# Eagle_4-Channel_Relay_Driver_Circuit.net
KiCad netlist of a schematic drawn in EAGLE
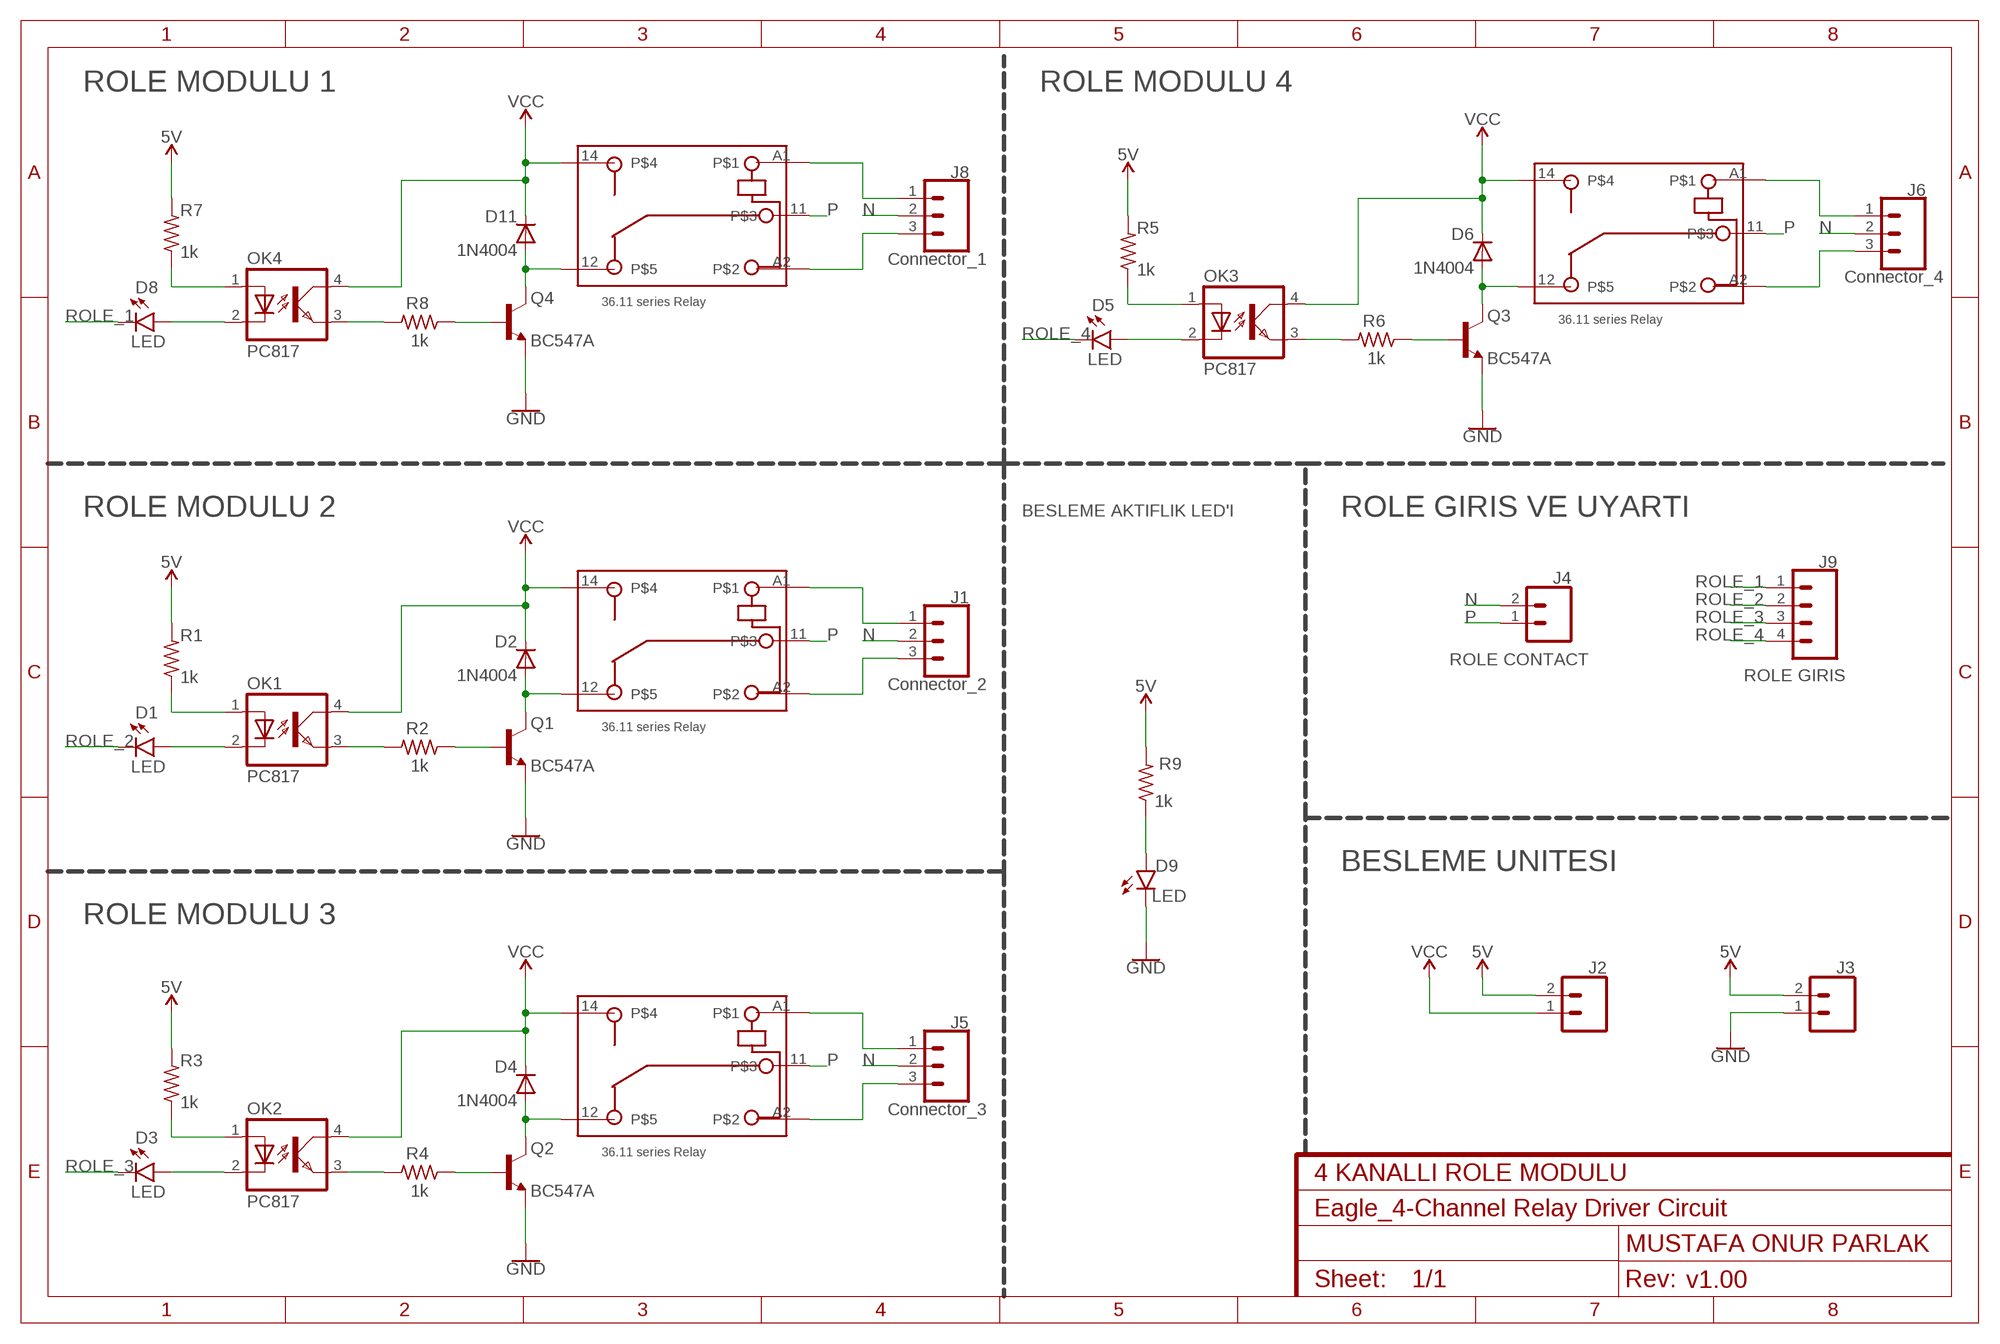
[diagram p0: schematic, sheet 1]

(export (version "E")
  (design (tool "Eeschema 10.0.6"))
  (components
    (comp (ref "D1")
      (value "LED")
      (footprint "eagle-import:LED_3MM")
      (libsource (lib "eagle-import") (part "LED3MM"))
    )
    (comp (ref "D2")
      (value "1N4004")
      (footprint "eagle-import:DO41-10")
      (libsource (lib "eagle-import") (part "1N4004"))
    )
    (comp (ref "D3")
      (value "LED")
      (footprint "eagle-import:LED_3MM")
      (libsource (lib "eagle-import") (part "LED3MM"))
    )
    (comp (ref "D4")
      (value "1N4004")
      (footprint "eagle-import:DO41-10")
      (libsource (lib "eagle-import") (part "1N4004"))
    )
    (comp (ref "D5")
      (value "LED")
      (footprint "eagle-import:LED_3MM")
      (libsource (lib "eagle-import") (part "LED3MM"))
    )
    (comp (ref "D6")
      (value "1N4004")
      (footprint "eagle-import:DO41-10")
      (libsource (lib "eagle-import") (part "1N4004"))
    )
    (comp (ref "D8")
      (value "LED")
      (footprint "eagle-import:LED_3MM")
      (libsource (lib "eagle-import") (part "LED3MM"))
    )
    (comp (ref "D9")
      (value "LED")
      (footprint "eagle-import:LED_3MM")
      (libsource (lib "eagle-import") (part "LED3MM"))
    )
    (comp (ref "D11")
      (value "1N4004")
      (footprint "eagle-import:DO41-10")
      (libsource (lib "eagle-import") (part "1N4004"))
    )
    (comp (ref "J1")
      (value "Connector_2")
      (footprint "eagle-import:1X03")
      (libsource (lib "eagle-import") (part "CONN_03"))
    )
    (comp (ref "J2")
      (value "CONN_02")
      (footprint "eagle-import:1X02")
      (libsource (lib "eagle-import") (part "CONN_02"))
    )
    (comp (ref "J3")
      (value "CONN_02")
      (footprint "eagle-import:1X02")
      (libsource (lib "eagle-import") (part "CONN_02"))
    )
    (comp (ref "J4")
      (value "ROLE CONTACT")
      (footprint "eagle-import:1X02")
      (libsource (lib "eagle-import") (part "CONN_02"))
    )
    (comp (ref "J5")
      (value "Connector_3")
      (footprint "eagle-import:1X03")
      (libsource (lib "eagle-import") (part "CONN_03"))
    )
    (comp (ref "J6")
      (value "Connector_4")
      (footprint "eagle-import:1X03")
      (libsource (lib "eagle-import") (part "CONN_03"))
    )
    (comp (ref "J8")
      (value "Connector_1")
      (footprint "eagle-import:1X03")
      (libsource (lib "eagle-import") (part "CONN_03"))
    )
    (comp (ref "J9")
      (value "ROLE GIRIS")
      (footprint "eagle-import:1X04")
      (libsource (lib "eagle-import") (part "CONN_04PTH"))
    )
    (comp (ref "OK1")
      (value "PC817")
      (footprint "eagle-import:DIL04")
      (libsource (lib "eagle-import") (part "PC817"))
    )
    (comp (ref "OK2")
      (value "PC817")
      (footprint "eagle-import:DIL04")
      (libsource (lib "eagle-import") (part "PC817"))
    )
    (comp (ref "OK3")
      (value "PC817")
      (footprint "eagle-import:DIL04")
      (libsource (lib "eagle-import") (part "PC817"))
    )
    (comp (ref "OK4")
      (value "PC817")
      (footprint "eagle-import:DIL04")
      (libsource (lib "eagle-import") (part "PC817"))
    )
    (comp (ref "Q1")
      (value "BC547A")
      (footprint "eagle-import:TO-92")
      (libsource (lib "eagle-import") (part "TRANS_NPN-2N3904"))
    )
    (comp (ref "Q2")
      (value "BC547A")
      (footprint "eagle-import:TO-92")
      (libsource (lib "eagle-import") (part "TRANS_NPN-2N3904"))
    )
    (comp (ref "Q3")
      (value "BC547A")
      (footprint "eagle-import:TO-92")
      (libsource (lib "eagle-import") (part "TRANS_NPN-2N3904"))
    )
    (comp (ref "Q4")
      (value "BC547A")
      (footprint "eagle-import:TO-92")
      (libsource (lib "eagle-import") (part "TRANS_NPN-2N3904"))
    )
    (comp (ref "R1")
      (value "1k")
      (footprint "eagle-import:0207_10")
      (libsource (lib "eagle-import") (part "R-US_0207/10"))
    )
    (comp (ref "R2")
      (value "1k")
      (footprint "eagle-import:0207_10")
      (libsource (lib "eagle-import") (part "R-US_0207/10"))
    )
    (comp (ref "R3")
      (value "1k")
      (footprint "eagle-import:0207_10")
      (libsource (lib "eagle-import") (part "R-US_0207/10"))
    )
    (comp (ref "R4")
      (value "1k")
      (footprint "eagle-import:0207_10")
      (libsource (lib "eagle-import") (part "R-US_0207/10"))
    )
    (comp (ref "R5")
      (value "1k")
      (footprint "eagle-import:0207_10")
      (libsource (lib "eagle-import") (part "R-US_0207/10"))
    )
    (comp (ref "R6")
      (value "1k")
      (footprint "eagle-import:0207_10")
      (libsource (lib "eagle-import") (part "R-US_0207/10"))
    )
    (comp (ref "R7")
      (value "1k")
      (footprint "eagle-import:0207_10")
      (libsource (lib "eagle-import") (part "R-US_0207/10"))
    )
    (comp (ref "R8")
      (value "1k")
      (footprint "eagle-import:0207_10")
      (libsource (lib "eagle-import") (part "R-US_0207/10"))
    )
    (comp (ref "R9")
      (value "1k")
      (footprint "eagle-import:0207_10")
      (libsource (lib "eagle-import") (part "R-US_0207/10"))
    )
    (comp (ref "ROLE_1")
      (value "36.11")
      (footprint "eagle-import:36.11")
      (libsource (lib "eagle-import") (part "36.11"))
    )
    (comp (ref "ROLE_2")
      (value "36.11")
      (footprint "eagle-import:36.11")
      (libsource (lib "eagle-import") (part "36.11"))
    )
    (comp (ref "ROLE_3")
      (value "36.11")
      (footprint "eagle-import:36.11")
      (libsource (lib "eagle-import") (part "36.11"))
    )
    (comp (ref "ROLE_4")
      (value "36.11")
      (footprint "eagle-import:36.11")
      (libsource (lib "eagle-import") (part "36.11"))
    )
  )
  (nets
    (net (code "1") (name "/N") (class "Default")
      (node (ref "J1") (pin "2") (pinfunction "2_2") (pintype "passive"))
      (node (ref "J4") (pin "2") (pinfunction "2_2") (pintype "passive"))
      (node (ref "J5") (pin "2") (pinfunction "2_2") (pintype "passive"))
      (node (ref "J6") (pin "2") (pinfunction "2_2") (pintype "passive"))
      (node (ref "J8") (pin "2") (pinfunction "2_2") (pintype "passive"))
    )
    (net (code "2") (name "/P") (class "Default")
      (node (ref "J4") (pin "1") (pinfunction "1_1") (pintype "passive"))
      (node (ref "ROLE_1") (pin "11") (pinfunction "P$3_11") (pintype "passive"))
      (node (ref "ROLE_2") (pin "11") (pinfunction "P$3_11") (pintype "passive"))
      (node (ref "ROLE_3") (pin "11") (pinfunction "P$3_11") (pintype "passive"))
      (node (ref "ROLE_4") (pin "11") (pinfunction "P$3_11") (pintype "passive"))
    )
    (net (code "3") (name "/ROLE_1") (class "Default")
      (node (ref "D8") (pin "K") (pinfunction "C_K") (pintype "passive"))
      (node (ref "J9") (pin "1") (pinfunction "1_1") (pintype "passive"))
    )
    (net (code "4") (name "/ROLE_2") (class "Default")
      (node (ref "D1") (pin "K") (pinfunction "C_K") (pintype "passive"))
      (node (ref "J9") (pin "2") (pinfunction "2_2") (pintype "passive"))
    )
    (net (code "5") (name "/ROLE_3") (class "Default")
      (node (ref "D3") (pin "K") (pinfunction "C_K") (pintype "passive"))
      (node (ref "J9") (pin "3") (pinfunction "3_3") (pintype "passive"))
    )
    (net (code "6") (name "/ROLE_4") (class "Default")
      (node (ref "D5") (pin "K") (pinfunction "C_K") (pintype "passive"))
      (node (ref "J9") (pin "4") (pinfunction "4_4") (pintype "passive"))
    )
    (net (code "7") (name "5V") (class "Default")
      (node (ref "J2") (pin "2") (pinfunction "2_2") (pintype "passive"))
      (node (ref "J3") (pin "2") (pinfunction "2_2") (pintype "passive"))
      (node (ref "R1") (pin "2") (pinfunction "2_2") (pintype "passive"))
      (node (ref "R3") (pin "2") (pinfunction "2_2") (pintype "passive"))
      (node (ref "R5") (pin "2") (pinfunction "2_2") (pintype "passive"))
      (node (ref "R7") (pin "2") (pinfunction "2_2") (pintype "passive"))
      (node (ref "R9") (pin "2") (pinfunction "2_2") (pintype "passive"))
    )
    (net (code "8") (name "GND") (class "Default")
      (node (ref "D9") (pin "K") (pinfunction "C_K") (pintype "passive"))
      (node (ref "J3") (pin "1") (pinfunction "1_1") (pintype "passive"))
      (node (ref "Q1") (pin "1") (pinfunction "E_1") (pintype "passive"))
      (node (ref "Q2") (pin "1") (pinfunction "E_1") (pintype "passive"))
      (node (ref "Q3") (pin "1") (pinfunction "E_1") (pintype "passive"))
      (node (ref "Q4") (pin "1") (pinfunction "E_1") (pintype "passive"))
    )
    (net (code "9") (name "Net-(D9-PadA)") (class "Default")
      (node (ref "D9") (pin "A") (pinfunction "A_A") (pintype "passive"))
      (node (ref "R9") (pin "1") (pinfunction "1_1") (pintype "passive"))
    )
    (net (code "10") (name "Net-(OK1-A)") (class "Default")
      (node (ref "OK1") (pin "1") (pinfunction "A_1") (pintype "passive"))
      (node (ref "R1") (pin "1") (pinfunction "1_1") (pintype "passive"))
    )
    (net (code "11") (name "Net-(OK1-C)") (class "Default")
      (node (ref "D1") (pin "A") (pinfunction "A_A") (pintype "passive"))
      (node (ref "OK1") (pin "2") (pinfunction "C_2") (pintype "passive"))
    )
    (net (code "12") (name "Net-(OK1-EMIT)") (class "Default")
      (node (ref "OK1") (pin "3") (pinfunction "EMIT_3") (pintype "passive"))
      (node (ref "R2") (pin "2") (pinfunction "2_2") (pintype "passive"))
    )
    (net (code "13") (name "Net-(OK2-A)") (class "Default")
      (node (ref "OK2") (pin "1") (pinfunction "A_1") (pintype "passive"))
      (node (ref "R3") (pin "1") (pinfunction "1_1") (pintype "passive"))
    )
    (net (code "14") (name "Net-(OK2-C)") (class "Default")
      (node (ref "D3") (pin "A") (pinfunction "A_A") (pintype "passive"))
      (node (ref "OK2") (pin "2") (pinfunction "C_2") (pintype "passive"))
    )
    (net (code "15") (name "Net-(OK2-EMIT)") (class "Default")
      (node (ref "OK2") (pin "3") (pinfunction "EMIT_3") (pintype "passive"))
      (node (ref "R4") (pin "2") (pinfunction "2_2") (pintype "passive"))
    )
    (net (code "16") (name "Net-(OK3-A)") (class "Default")
      (node (ref "OK3") (pin "1") (pinfunction "A_1") (pintype "passive"))
      (node (ref "R5") (pin "1") (pinfunction "1_1") (pintype "passive"))
    )
    (net (code "17") (name "Net-(OK3-C)") (class "Default")
      (node (ref "D5") (pin "A") (pinfunction "A_A") (pintype "passive"))
      (node (ref "OK3") (pin "2") (pinfunction "C_2") (pintype "passive"))
    )
    (net (code "18") (name "Net-(OK3-EMIT)") (class "Default")
      (node (ref "OK3") (pin "3") (pinfunction "EMIT_3") (pintype "passive"))
      (node (ref "R6") (pin "2") (pinfunction "2_2") (pintype "passive"))
    )
    (net (code "19") (name "Net-(OK4-A)") (class "Default")
      (node (ref "OK4") (pin "1") (pinfunction "A_1") (pintype "passive"))
      (node (ref "R7") (pin "1") (pinfunction "1_1") (pintype "passive"))
    )
    (net (code "20") (name "Net-(OK4-C)") (class "Default")
      (node (ref "D8") (pin "A") (pinfunction "A_A") (pintype "passive"))
      (node (ref "OK4") (pin "2") (pinfunction "C_2") (pintype "passive"))
    )
    (net (code "21") (name "Net-(OK4-EMIT)") (class "Default")
      (node (ref "OK4") (pin "3") (pinfunction "EMIT_3") (pintype "passive"))
      (node (ref "R8") (pin "2") (pinfunction "2_2") (pintype "passive"))
    )
    (net (code "22") (name "Net-(Q1-B)") (class "Default")
      (node (ref "Q1") (pin "2") (pinfunction "B_2") (pintype "passive"))
      (node (ref "R2") (pin "1") (pinfunction "1_1") (pintype "passive"))
    )
    (net (code "23") (name "Net-(Q1-C)") (class "Default")
      (node (ref "D2") (pin "A") (pinfunction "A_A") (pintype "passive"))
      (node (ref "Q1") (pin "3") (pinfunction "C_3") (pintype "passive"))
      (node (ref "ROLE_2") (pin "12") (pinfunction "P$5_12") (pintype "passive"))
    )
    (net (code "24") (name "Net-(Q2-B)") (class "Default")
      (node (ref "Q2") (pin "2") (pinfunction "B_2") (pintype "passive"))
      (node (ref "R4") (pin "1") (pinfunction "1_1") (pintype "passive"))
    )
    (net (code "25") (name "Net-(Q2-C)") (class "Default")
      (node (ref "D4") (pin "A") (pinfunction "A_A") (pintype "passive"))
      (node (ref "Q2") (pin "3") (pinfunction "C_3") (pintype "passive"))
      (node (ref "ROLE_3") (pin "12") (pinfunction "P$5_12") (pintype "passive"))
    )
    (net (code "26") (name "Net-(Q3-B)") (class "Default")
      (node (ref "Q3") (pin "2") (pinfunction "B_2") (pintype "passive"))
      (node (ref "R6") (pin "1") (pinfunction "1_1") (pintype "passive"))
    )
    (net (code "27") (name "Net-(Q3-C)") (class "Default")
      (node (ref "D6") (pin "A") (pinfunction "A_A") (pintype "passive"))
      (node (ref "Q3") (pin "3") (pinfunction "C_3") (pintype "passive"))
      (node (ref "ROLE_4") (pin "12") (pinfunction "P$5_12") (pintype "passive"))
    )
    (net (code "28") (name "Net-(Q4-B)") (class "Default")
      (node (ref "Q4") (pin "2") (pinfunction "B_2") (pintype "passive"))
      (node (ref "R8") (pin "1") (pinfunction "1_1") (pintype "passive"))
    )
    (net (code "29") (name "Net-(Q4-C)") (class "Default")
      (node (ref "D11") (pin "A") (pinfunction "A_A") (pintype "passive"))
      (node (ref "Q4") (pin "3") (pinfunction "C_3") (pintype "passive"))
      (node (ref "ROLE_1") (pin "12") (pinfunction "P$5_12") (pintype "passive"))
    )
    (net (code "30") (name "Net-(ROLE_1-P$1)") (class "Default")
      (node (ref "J8") (pin "1") (pinfunction "1_1") (pintype "passive"))
      (node (ref "ROLE_1") (pin "A1") (pinfunction "P$1_A1") (pintype "passive"))
    )
    (net (code "31") (name "Net-(ROLE_1-P$2)") (class "Default")
      (node (ref "J8") (pin "3") (pinfunction "3_3") (pintype "passive"))
      (node (ref "ROLE_1") (pin "A2") (pinfunction "P$2_A2") (pintype "passive"))
    )
    (net (code "32") (name "Net-(ROLE_2-P$1)") (class "Default")
      (node (ref "J1") (pin "1") (pinfunction "1_1") (pintype "passive"))
      (node (ref "ROLE_2") (pin "A1") (pinfunction "P$1_A1") (pintype "passive"))
    )
    (net (code "33") (name "Net-(ROLE_2-P$2)") (class "Default")
      (node (ref "J1") (pin "3") (pinfunction "3_3") (pintype "passive"))
      (node (ref "ROLE_2") (pin "A2") (pinfunction "P$2_A2") (pintype "passive"))
    )
    (net (code "34") (name "Net-(ROLE_3-P$1)") (class "Default")
      (node (ref "J5") (pin "1") (pinfunction "1_1") (pintype "passive"))
      (node (ref "ROLE_3") (pin "A1") (pinfunction "P$1_A1") (pintype "passive"))
    )
    (net (code "35") (name "Net-(ROLE_3-P$2)") (class "Default")
      (node (ref "J5") (pin "3") (pinfunction "3_3") (pintype "passive"))
      (node (ref "ROLE_3") (pin "A2") (pinfunction "P$2_A2") (pintype "passive"))
    )
    (net (code "36") (name "Net-(ROLE_4-P$1)") (class "Default")
      (node (ref "J6") (pin "1") (pinfunction "1_1") (pintype "passive"))
      (node (ref "ROLE_4") (pin "A1") (pinfunction "P$1_A1") (pintype "passive"))
    )
    (net (code "37") (name "Net-(ROLE_4-P$2)") (class "Default")
      (node (ref "J6") (pin "3") (pinfunction "3_3") (pintype "passive"))
      (node (ref "ROLE_4") (pin "A2") (pinfunction "P$2_A2") (pintype "passive"))
    )
    (net (code "38") (name "VCC") (class "Default")
      (node (ref "D11") (pin "C") (pinfunction "C_C") (pintype "passive"))
      (node (ref "D2") (pin "C") (pinfunction "C_C") (pintype "passive"))
      (node (ref "D4") (pin "C") (pinfunction "C_C") (pintype "passive"))
      (node (ref "D6") (pin "C") (pinfunction "C_C") (pintype "passive"))
      (node (ref "J2") (pin "1") (pinfunction "1_1") (pintype "passive"))
      (node (ref "OK1") (pin "4") (pinfunction "COL_4") (pintype "passive"))
      (node (ref "OK2") (pin "4") (pinfunction "COL_4") (pintype "passive"))
      (node (ref "OK3") (pin "4") (pinfunction "COL_4") (pintype "passive"))
      (node (ref "OK4") (pin "4") (pinfunction "COL_4") (pintype "passive"))
      (node (ref "ROLE_1") (pin "14") (pinfunction "P$4_14") (pintype "passive"))
      (node (ref "ROLE_2") (pin "14") (pinfunction "P$4_14") (pintype "passive"))
      (node (ref "ROLE_3") (pin "14") (pinfunction "P$4_14") (pintype "passive"))
      (node (ref "ROLE_4") (pin "14") (pinfunction "P$4_14") (pintype "passive"))
    )
  )
)
